# design.net
KiCad netlist of a schematic drawn in Altium Designer
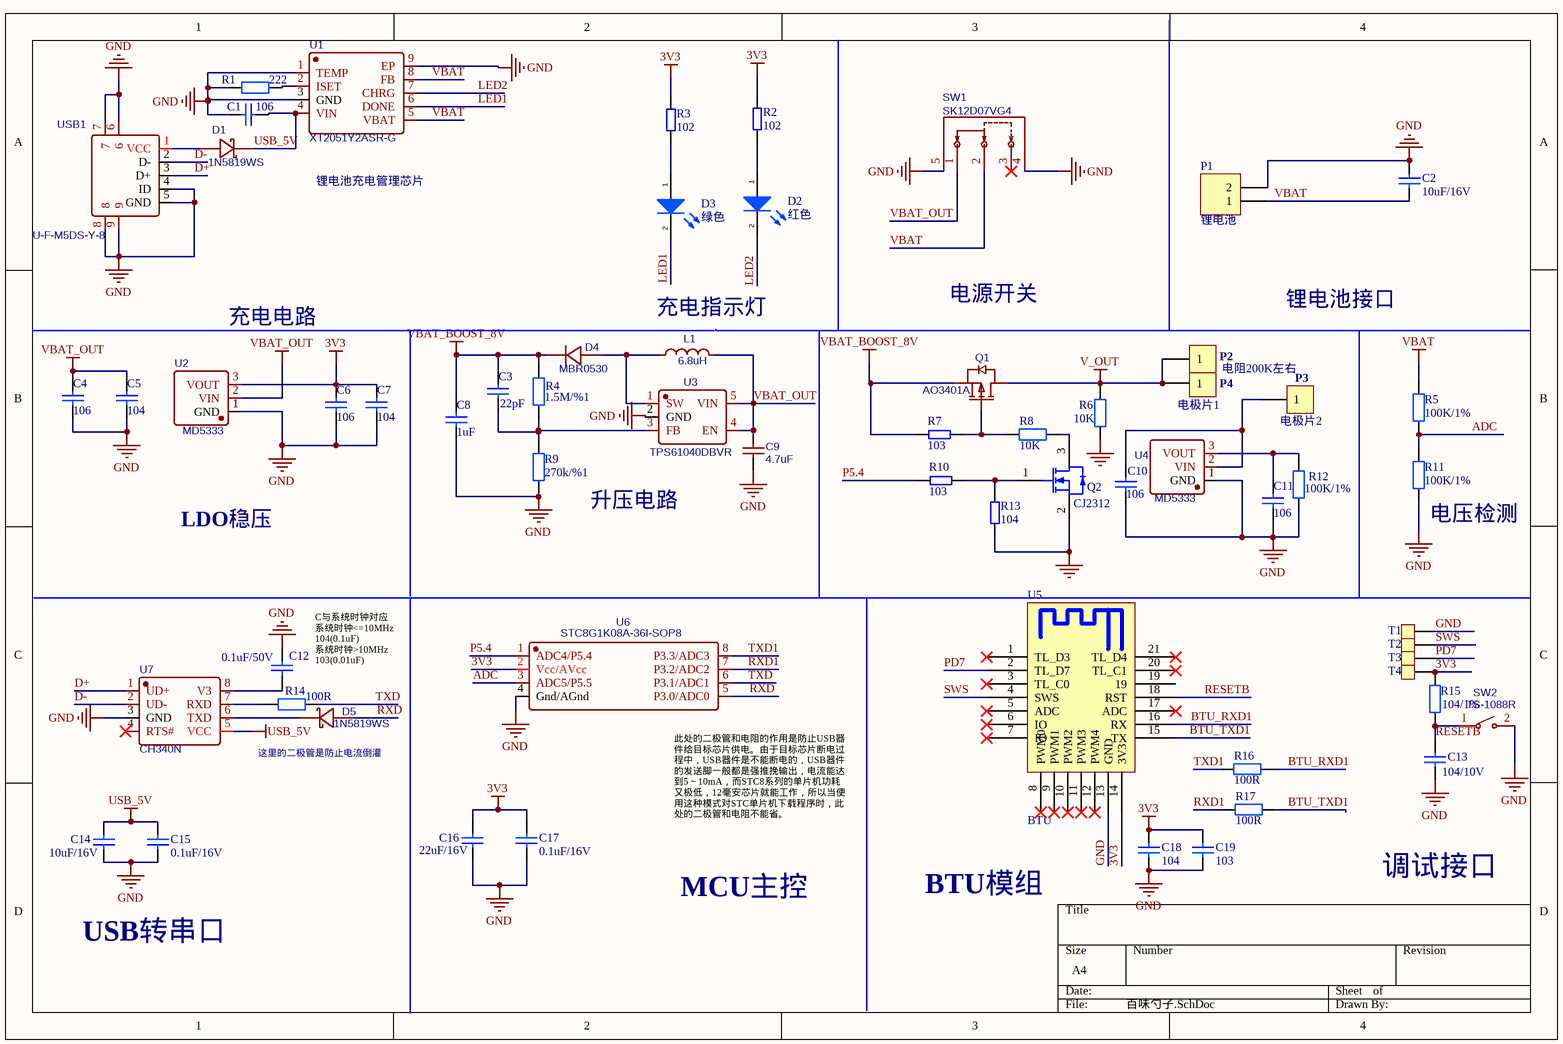
[diagram p0: 百味勺子.SchDoc]

(export (version "E")
  (design (tool "Eeschema 10.0.6"))
  (components
    (comp (ref "C1")
      (value "106")
      (footprint "C0603")
      (description "无极性电容")
      (fields (field (name "PART NUMBER") "1.02.03.00181") (field (name "修改人") "system"))
      (libsource (lib "Database_Libs") (part "Capacitor - non polarized"))
    )
    (comp (ref "C2")
      (value "10uF/16V")
      (footprint "C0603")
      (description "无极性电容")
      (fields (field (name "PART NUMBER") "1.02.05.00869"))
      (libsource (lib "咸味勺子-20210715") (part "Capacitor - non polarized"))
    )
    (comp (ref "C3")
      (value "22pF")
      (footprint "C0402")
      (description "无极性电容")
      (fields (field (name "PART NUMBER") "1.02.05.00869"))
      (libsource (lib "Database_Libs4") (part "Capacitor - non polarized"))
    )
    (comp (ref "C4")
      (value "106")
      (footprint "C0603")
      (description "无极性电容")
      (fields (field (name "PART NUMBER") "1.02.05.00869"))
      (libsource (lib "Database_Libs4") (part "Capacitor - non polarized"))
    )
    (comp (ref "C5")
      (value "104")
      (footprint "C0402")
      (description "无极性电容")
      (fields (field (name "PART NUMBER") "1.02.05.00869"))
      (libsource (lib "Database_Libs4") (part "Capacitor - non polarized"))
    )
    (comp (ref "C6")
      (value "106")
      (footprint "C0603")
      (description "无极性电容")
      (fields (field (name "PART NUMBER") "1.02.05.00869"))
      (libsource (lib "Database_Libs4") (part "Capacitor - non polarized"))
    )
    (comp (ref "C7")
      (value "104")
      (footprint "C0402")
      (description "无极性电容")
      (fields (field (name "PART NUMBER") "1.02.05.00869"))
      (libsource (lib "Database_Libs4") (part "Capacitor - non polarized"))
    )
    (comp (ref "C8")
      (value "1uF")
      (footprint "C0603")
      (description "无极性电容")
      (fields (field (name "PART NUMBER") "1.02.05.00869"))
      (libsource (lib "Database_Libs4") (part "Capacitor - non polarized"))
    )
    (comp (ref "C9")
      (value "4.7uF")
      (footprint "JMK212BJ475KG-T")
      (fields
        (field (name "BOM_MANUFACTURER PART") "JMK212BJ475KG-T")
        (field (name "BOM_SUPPLIER PART") "C92788")
      )
      (libsource (lib "altium-import") (part "root_1_4.7uF_"))
    )
    (comp (ref "C10")
      (value "106")
      (footprint "C0603")
      (description "无极性电容")
      (fields (field (name "PART NUMBER") "1.02.05.00869"))
      (libsource (lib "Database_Libs4") (part "Capacitor - non polarized"))
    )
    (comp (ref "C11")
      (value "106")
      (footprint "C0603")
      (description "无极性电容")
      (fields (field (name "PART NUMBER") "1.02.05.00869"))
      (libsource (lib "Database_Libs4") (part "Capacitor - non polarized"))
    )
    (comp (ref "C12")
      (value "0.1uF/50V")
      (footprint "C0402")
      (description "无极性电容")
      (fields (field (name "PART NUMBER") "1.02.05.00834") (field (name "修改人") "system"))
      (libsource (lib "Database_Libs") (part "Capacitor - non polarized"))
    )
    (comp (ref "C13")
      (value "104/10V")
      (footprint "C0402")
      (description "无极性电容")
      (fields (field (name "PART NUMBER") "1.02.05.00869"))
      (libsource (lib "Database_Libs4") (part "Capacitor - non polarized"))
    )
    (comp (ref "C14")
      (value "10uF/16V")
      (footprint "C0603")
      (description "无极性电容")
      (fields (field (name "PART NUMBER") "1.02.03.00181") (field (name "修改人") "system"))
      (libsource (lib "Database_Libs") (part "Capacitor - non polarized"))
    )
    (comp (ref "C15")
      (value "0.1uF/16V")
      (footprint "C0402")
      (description "无极性电容")
      (fields (field (name "PART NUMBER") "1.02.05.00834") (field (name "修改人") "system"))
      (libsource (lib "Database_Libs") (part "Capacitor - non polarized"))
    )
    (comp (ref "C16")
      (value "22uF/16V")
      (footprint "C0603")
      (description "无极性电容")
      (fields (field (name "PART NUMBER") "1.02.03.00181") (field (name "修改人") "system"))
      (libsource (lib "Database_Libs") (part "Capacitor - non polarized"))
    )
    (comp (ref "C17")
      (value "0.1uF/16V")
      (footprint "C0402")
      (description "无极性电容")
      (fields (field (name "PART NUMBER") "1.02.05.00834") (field (name "修改人") "system"))
      (libsource (lib "Database_Libs") (part "Capacitor - non polarized"))
    )
    (comp (ref "C18")
      (value "104")
      (footprint "C0402")
      (description "无极性电容")
      (fields (field (name "PART NUMBER") "1.02.05.00869"))
      (libsource (lib "Database_Libs4") (part "Capacitor - non polarized"))
    )
    (comp (ref "C19")
      (value "103")
      (footprint "C0402")
      (description "无极性电容")
      (fields (field (name "PART NUMBER") "1.02.05.00869"))
      (libsource (lib "Database_Libs4") (part "Capacitor - non polarized"))
    )
    (comp (ref "D1")
      (value "1N5819WS")
      (footprint "1N5819WS")
      (fields (field (name "BOM_SUPPLIER PART") "C1884554") (field (name "CONTRIBUTOR") "LCSC"))
      (libsource (lib "altium-import") (part "root_2_1N5819WS_C1884554_"))
    )
    (comp (ref "D2")
      (value "红色")
      (footprint "OSR50603C1E")
      (description "LED")
      (fields (field (name "PART NUMBER") "1.06.02.00452"))
      (libsource (lib "咸味勺子-20210715") (part "LED"))
    )
    (comp (ref "D3")
      (value "绿色")
      (footprint "OSR50603C1E")
      (description "LED")
      (fields (field (name "PART NUMBER") "1.06.02.00452"))
      (libsource (lib "咸味勺子-20210715") (part "LED"))
    )
    (comp (ref "D4")
      (value "MBR0530")
      (footprint "MBR0530")
      (fields (field (name "BOM_SUPPLIER PART") "C475718") (field (name "CONTRIBUTOR") "LCSC"))
      (libsource (lib "altium-import") (part "root_0_MBR0530_C475718_"))
    )
    (comp (ref "D5")
      (value "1N5819WS")
      (footprint "1N5819WS")
      (fields (field (name "BOM_SUPPLIER PART") "C1884554") (field (name "CONTRIBUTOR") "LCSC"))
      (libsource (lib "altium-import") (part "root_0_1N5819WS_C1884554_"))
    )
    (comp (ref "L1")
      (value "6.8uH")
      (footprint "CDRH3D23NP-6R8PC")
      (fields
        (field (name "BOM_SUPPLIER PART") "C323532")
        (field (name "BOM_MANUFACTURER PART") "CDRH3D23NP-6R8PC")
        (field (name "CONTRIBUTOR") "LCSC")
      )
      (libsource (lib "altium-import") (part "root_0_6.8uH_"))
    )
    (comp (ref "P1")
      (value "锂电池")
      (footprint "HDR1X2")
      (description "Header, 2-Pin")
      (fields (field (name "PUBLISHER") "Altium Limited"))
      (libsource (lib "Miscellaneous Connectors") (part "Header 2"))
    )
    (comp (ref "P2") (value "CON1") (footprint "焊点1") (libsource (lib "智能烧水壶 -电源板") (part "CON1")))
    (comp (ref "P3") (value "CON1") (footprint "焊点1") (libsource (lib "智能烧水壶 -电源板") (part "CON1")))
    (comp (ref "P4") (value "CON1") (footprint "焊点1") (libsource (lib "智能烧水壶 -电源板") (part "CON1")))
    (comp (ref "Q1")
      (value "AO3401A")
      (footprint "AO3401A")
      (fields (field (name "BOM_SUPPLIER PART") "C700954") (field (name "CONTRIBUTOR") "LCSC"))
      (libsource (lib "altium-import") (part "root_1_mirrored_AO3401A_C700954_"))
    )
    (comp (ref "Q2")
      (value "CJ2312")
      (footprint "CJ2312")
      (description "N-Channel MOSFET")
      (fields
        (field (name "PART NUMBER") "1.06.11.00008")
        (field (name "ORCAD LIBRARY PATH") "‪Z:\\tuya_lib\\sch-lib\\DISCRETE.OLB")
        (field (name "修改人") "system")
      )
      (libsource (lib "Database_Libs") (part "MOSFET-N"))
    )
    (comp (ref "R1")
      (value "222")
      (footprint "R0402")
      (description "电阻")
      (fields (field (name "PART NUMBER") "1.01.01.00808"))
      (libsource (lib "Database_Libs4") (part "Resistor"))
    )
    (comp (ref "R2")
      (value "102")
      (footprint "R0402")
      (description "RES")
      (libsource (lib "咸味勺子-20210715") (part "RES-1"))
    )
    (comp (ref "R3")
      (value "102")
      (footprint "R0402")
      (description "RES")
      (libsource (lib "咸味勺子-20210715") (part "RES-1"))
    )
    (comp (ref "R4")
      (value "1.5M/%1")
      (footprint "R0402")
      (description "电阻")
      (libsource (lib "Database_Libs") (part "Resistor"))
    )
    (comp (ref "R5")
      (value "100K/1%")
      (footprint "R0402")
      (description "电阻")
      (libsource (lib "Database_Libs") (part "Resistor"))
    )
    (comp (ref "R6")
      (value "10K")
      (footprint "R0402")
      (description "电阻")
      (libsource (lib "") (part "Resistor_2"))
    )
    (comp (ref "R7")
      (value "103")
      (footprint "R0402")
      (description "RES")
      (libsource (lib "先锋器件封装库") (part "RES-1"))
    )
    (comp (ref "R8")
      (value "10K")
      (footprint "R0402")
      (description "电阻")
      (libsource (lib "") (part "Resistor_1"))
    )
    (comp (ref "R9")
      (value "270k/%1")
      (footprint "R0402")
      (description "电阻")
      (libsource (lib "Database_Libs") (part "Resistor"))
    )
    (comp (ref "R10")
      (value "103")
      (footprint "R0402")
      (description "RES")
      (libsource (lib "先锋器件封装库") (part "RES-1"))
    )
    (comp (ref "R11")
      (value "100K/1%")
      (footprint "R0402")
      (description "电阻")
      (libsource (lib "Database_Libs") (part "Resistor"))
    )
    (comp (ref "R12")
      (value "100K/1%")
      (footprint "R0402")
      (description "电阻")
      (libsource (lib "Database_Libs") (part "Resistor"))
    )
    (comp (ref "R13")
      (value "104")
      (footprint "R0402")
      (description "RES")
      (libsource (lib "先锋器件封装库") (part "RES-1"))
    )
    (comp (ref "R14")
      (value "100R")
      (footprint "R0402")
      (description "电阻")
      (fields (field (name "PART NUMBER") "1.01.01.00808") (field (name "修改人") "system"))
      (libsource (lib "") (part "Resistor_1"))
    )
    (comp (ref "R15")
      (value "104/1%")
      (footprint "R0402")
      (description "电阻")
      (fields (field (name "PART NUMBER") "1.01.01.00808"))
      (libsource (lib "") (part "Resistor_1"))
    )
    (comp (ref "R16")
      (value "100R")
      (footprint "R0402")
      (description "电阻")
      (fields (field (name "PART NUMBER") "1.01.01.00808"))
      (libsource (lib "Database_Libs4") (part "Resistor"))
    )
    (comp (ref "R17")
      (value "100R")
      (footprint "R0402")
      (description "电阻")
      (fields (field (name "PART NUMBER") "1.01.01.00808"))
      (libsource (lib "Database_Libs4") (part "Resistor"))
    )
    (comp (ref "SW1")
      (value "SK12D07VG4")
      (footprint "SK12D07VG4")
      (fields (field (name "BOM_SUPPLIER PART") "C393937") (field (name "CONTRIBUTOR") "LCSC"))
      (libsource (lib "咸味勺子-20210715") (part "SK12D07VG4"))
    )
    (comp (ref "SW2")
      (value "TS-1088R")
      (footprint "TS-1088R-02026")
      (fields
        (field (name "BOM_SUPPLIER PART") "C455280")
        (field (name "BOM_MANUFACTURER PART") "TS-1088R-02026")
        (field (name "CONTRIBUTOR") "LCSC")
      )
      (libsource (lib "altium-import") (part "root_0_TS-1088R-02026_"))
    )
    (comp (ref "T1") (value "TP") (footprint "TP1") (libsource (lib "MIAXIS-SCH") (part "TP")))
    (comp (ref "T2") (value "TP") (footprint "TP1") (libsource (lib "MIAXIS-SCH") (part "TP")))
    (comp (ref "T3") (value "TP") (footprint "TP1") (libsource (lib "MIAXIS-SCH") (part "TP")))
    (comp (ref "T4") (value "TP") (footprint "TP1") (libsource (lib "MIAXIS-SCH") (part "TP")))
    (comp (ref "U1")
      (value "XT2051Y2ASR-G")
      (footprint "XT2051Y2ASR-G")
      (fields (field (name "BOM_SUPPLIER PART") "C236398") (field (name "CONTRIBUTOR") "LCSC"))
      (libsource (lib "altium-import") (part "root_0_XT2051Y2ASR-G_"))
    )
    (comp (ref "U2")
      (value "MD5333")
      (footprint "MD5333")
      (fields (field (name "BOM_SUPPLIER PART") "C2827936") (field (name "CONTRIBUTOR") "LCSC"))
      (libsource (lib "altium-import") (part "root_2_MD5333_"))
    )
    (comp (ref "U3")
      (value "TPS61040DBVR")
      (footprint "TPS61040DBVR")
      (fields (field (name "BOM_SUPPLIER PART") "C7722"))
      (libsource (lib "altium-import") (part "root_0_TPS61040DBVR_"))
    )
    (comp (ref "U4")
      (value "MD5333")
      (footprint "MD5333")
      (fields (field (name "BOM_SUPPLIER PART") "C2827936") (field (name "CONTRIBUTOR") "LCSC"))
      (libsource (lib "altium-import") (part "root_2_MD5333_"))
    )
    (comp (ref "U5")
      (value "BTU")
      (footprint "CBU1")
      (fields (field (name "PART NUMBER") "0110"))
      (libsource (lib "BTU_V100") (part "CBU"))
    )
    (comp (ref "U6")
      (value "STC8G1K08A-36I-SOP8")
      (footprint "STC8G1K08A-36I-SOP8")
      (fields (field (name "BOM_SUPPLIER PART") "C915663") (field (name "CONTRIBUTOR") "LCSC"))
      (libsource (lib "altium-import") (part "root_0_STC8G1K08A-36I-SOP8_"))
    )
    (comp (ref "U7")
      (value "CH340N")
      (footprint "CH340N")
      (fields (field (name "BOM_SUPPLIER PART") "C506813") (field (name "CONTRIBUTOR") "LCSC"))
      (libsource (lib "TY") (part "CH340N"))
    )
    (comp (ref "USB1")
      (value "U-F-M5DS-Y-8")
      (footprint "U-F-M5DS-Y-8")
      (fields (field (name "BOM_SUPPLIER PART") "C961761") (field (name "CONTRIBUTOR") "LCSC"))
      (libsource (lib "altium-import") (part "root_0_U-F-M5DS-Y-8_"))
    )
  )
  (nets
    (net (code "1") (name "/ADC") (class "Default")
      (node (ref "R11") (pin "2") (pinfunction "2_2") (pintype "passive"))
      (node (ref "R5") (pin "1") (pinfunction "1_1") (pintype "passive"))
      (node (ref "U6") (pin "3") (pinfunction "ADC5/P5.5_3") (pintype "passive"))
    )
    (net (code "2") (name "/BTU_RXD1") (class "Default")
      (node (ref "R16") (pin "1") (pinfunction "1_1") (pintype "passive"))
      (node (ref "U5") (pin "16") (pinfunction "RX_16") (pintype "passive"))
    )
    (net (code "3") (name "/BTU_TXD1") (class "Default")
      (node (ref "R17") (pin "1") (pinfunction "1_1") (pintype "passive"))
      (node (ref "U5") (pin "15") (pinfunction "TX_15") (pintype "passive"))
    )
    (net (code "4") (name "/D+") (class "Default")
      (node (ref "U7") (pin "1") (pinfunction "UD+_1") (pintype "passive"))
      (node (ref "USB1") (pin "3") (pinfunction "D+_3") (pintype "passive"))
    )
    (net (code "5") (name "/D-") (class "Default")
      (node (ref "U7") (pin "2") (pinfunction "UD-_2") (pintype "passive"))
      (node (ref "USB1") (pin "2") (pinfunction "D-_2") (pintype "passive"))
    )
    (net (code "6") (name "/LED1") (class "Default")
      (node (ref "D3") (pin "2") (pinfunction "2_2") (pintype "passive"))
      (node (ref "U1") (pin "6") (pinfunction "DONE_6") (pintype "passive"))
    )
    (net (code "7") (name "/LED2") (class "Default")
      (node (ref "D2") (pin "2") (pinfunction "2_2") (pintype "passive"))
      (node (ref "U1") (pin "7") (pinfunction "CHRG_7") (pintype "passive"))
    )
    (net (code "8") (name "/P5.4") (class "Default")
      (node (ref "R10") (pin "1") (pintype "passive"))
      (node (ref "U6") (pin "1") (pinfunction "ADC4/P5.4_1") (pintype "passive"))
    )
    (net (code "9") (name "/PD7") (class "Default")
      (node (ref "T3") (pin "1") (pinfunction "1_1") (pintype "passive"))
      (node (ref "U5") (pin "2") (pinfunction "TL_D7_2") (pintype "passive"))
    )
    (net (code "10") (name "/RESETB") (class "Default")
      (node (ref "C13") (pin "1") (pinfunction "1_1") (pintype "passive"))
      (node (ref "R15") (pin "1") (pinfunction "1_1") (pintype "passive"))
      (node (ref "SW2") (pin "1") (pinfunction "1_1") (pintype "passive"))
      (node (ref "U5") (pin "18") (pinfunction "RST_18") (pintype "passive"))
    )
    (net (code "11") (name "/RXD") (class "Default")
      (node (ref "D5") (pin "2") (pinfunction "A_2") (pintype "passive"))
      (node (ref "U6") (pin "5") (pinfunction "P3.0/ADC0_5") (pintype "passive"))
    )
    (net (code "12") (name "/RXD1") (class "Default")
      (node (ref "R17") (pin "2") (pinfunction "2_2") (pintype "passive"))
      (node (ref "U6") (pin "7") (pinfunction "P3.2/ADC2_7") (pintype "passive"))
    )
    (net (code "13") (name "/SWS") (class "Default")
      (node (ref "T2") (pin "1") (pinfunction "1_1") (pintype "passive"))
      (node (ref "U5") (pin "4") (pinfunction "SWS_4") (pintype "passive"))
    )
    (net (code "14") (name "/TXD") (class "Default")
      (node (ref "R14") (pin "2") (pinfunction "2_2") (pintype "passive"))
      (node (ref "U6") (pin "6") (pinfunction "P3.1/ADC1_6") (pintype "passive"))
    )
    (net (code "15") (name "/TXD1") (class "Default")
      (node (ref "R16") (pin "2") (pinfunction "2_2") (pintype "passive"))
      (node (ref "U6") (pin "8") (pinfunction "P3.3/ADC3_8") (pintype "passive"))
    )
    (net (code "16") (name "3V3") (class "Default")
      (node (ref "C16") (pin "2") (pinfunction "2_2") (pintype "passive"))
      (node (ref "C17") (pin "2") (pinfunction "2_2") (pintype "passive"))
      (node (ref "C18") (pin "1") (pinfunction "1_1") (pintype "passive"))
      (node (ref "C19") (pin "1") (pinfunction "1_1") (pintype "passive"))
      (node (ref "C6") (pin "1") (pinfunction "1_1") (pintype "passive"))
      (node (ref "C7") (pin "1") (pinfunction "1_1") (pintype "passive"))
      (node (ref "R15") (pin "2") (pinfunction "2_2") (pintype "passive"))
      (node (ref "R2") (pin "2") (pintype "passive"))
      (node (ref "R3") (pin "2") (pintype "passive"))
      (node (ref "T4") (pin "1") (pinfunction "1_1") (pintype "passive"))
      (node (ref "U2") (pin "3") (pinfunction "VOUT_3") (pintype "passive"))
      (node (ref "U5") (pin "14") (pinfunction "3V3_14") (pintype "passive"))
      (node (ref "U6") (pin "2") (pinfunction "Vcc/AVcc_2") (pintype "passive"))
    )
    (net (code "17") (name "GND") (class "Default")
      (node (ref "C1") (pin "2") (pinfunction "2_2") (pintype "passive"))
      (node (ref "C10") (pin "2") (pinfunction "2_2") (pintype "passive"))
      (node (ref "C11") (pin "2") (pinfunction "2_2") (pintype "passive"))
      (node (ref "C12") (pin "2") (pinfunction "2_2") (pintype "passive"))
      (node (ref "C13") (pin "2") (pinfunction "2_2") (pintype "passive"))
      (node (ref "C14") (pin "1") (pinfunction "1_1") (pintype "passive"))
      (node (ref "C15") (pin "1") (pinfunction "1_1") (pintype "passive"))
      (node (ref "C16") (pin "1") (pinfunction "1_1") (pintype "passive"))
      (node (ref "C17") (pin "1") (pinfunction "1_1") (pintype "passive"))
      (node (ref "C18") (pin "2") (pinfunction "2_2") (pintype "passive"))
      (node (ref "C19") (pin "2") (pinfunction "2_2") (pintype "passive"))
      (node (ref "C2") (pin "1") (pinfunction "1_1") (pintype "passive"))
      (node (ref "C4") (pin "2") (pinfunction "2_2") (pintype "passive"))
      (node (ref "C5") (pin "2") (pinfunction "2_2") (pintype "passive"))
      (node (ref "C6") (pin "2") (pinfunction "2_2") (pintype "passive"))
      (node (ref "C7") (pin "2") (pinfunction "2_2") (pintype "passive"))
      (node (ref "C8") (pin "2") (pinfunction "2_2") (pintype "passive"))
      (node (ref "C9") (pin "1") (pinfunction "1_1") (pintype "passive"))
      (node (ref "P1") (pin "2") (pinfunction "2_2") (pintype "passive"))
      (node (ref "Q2") (pin "2") (pinfunction "S_2") (pintype "passive"))
      (node (ref "R1") (pin "2") (pinfunction "2_2") (pintype "passive"))
      (node (ref "R11") (pin "1") (pinfunction "1_1") (pintype "passive"))
      (node (ref "R12") (pin "1") (pinfunction "1_1") (pintype "passive"))
      (node (ref "R13") (pin "1") (pintype "passive"))
      (node (ref "R6") (pin "2") (pinfunction "2_2") (pintype "passive"))
      (node (ref "R9") (pin "1") (pinfunction "1_1") (pintype "passive"))
      (node (ref "SW1") (pin "4") (pinfunction "4_4") (pintype "passive"))
      (node (ref "SW1") (pin "5") (pinfunction "5_5") (pintype "passive"))
      (node (ref "SW2") (pin "2") (pinfunction "2_2") (pintype "passive"))
      (node (ref "T1") (pin "1") (pinfunction "1_1") (pintype "passive"))
      (node (ref "U1") (pin "1") (pinfunction "TEMP_1") (pintype "passive"))
      (node (ref "U1") (pin "3") (pinfunction "GND_3") (pintype "passive"))
      (node (ref "U1") (pin "9") (pinfunction "EP_9") (pintype "passive"))
      (node (ref "U2") (pin "1") (pinfunction "GND_1") (pintype "passive"))
      (node (ref "U3") (pin "2") (pinfunction "GND_2") (pintype "passive"))
      (node (ref "U4") (pin "1") (pinfunction "GND_1") (pintype "passive"))
      (node (ref "U5") (pin "13") (pinfunction "GND_13") (pintype "passive"))
      (node (ref "U6") (pin "4") (pinfunction "Gnd/AGnd_4") (pintype "passive"))
      (node (ref "U7") (pin "3") (pinfunction "GND_3") (pintype "passive"))
      (node (ref "USB1") (pin "4") (pinfunction "ID_4") (pintype "passive"))
      (node (ref "USB1") (pin "5") (pinfunction "GND_5") (pintype "passive"))
      (node (ref "USB1") (pin "6") (pinfunction "6_6") (pintype "passive"))
      (node (ref "USB1") (pin "7") (pinfunction "7_7") (pintype "passive"))
      (node (ref "USB1") (pin "8") (pinfunction "8_8") (pintype "passive"))
      (node (ref "USB1") (pin "9") (pinfunction "9_9") (pintype "passive"))
    )
    (net (code "18") (name "Net-(D1-A)") (class "Default")
      (node (ref "D1") (pin "2") (pinfunction "A_2") (pintype "passive"))
      (node (ref "USB1") (pin "1") (pinfunction "VCC_1") (pintype "passive"))
    )
    (net (code "19") (name "Net-(D2-Pad1)") (class "Default")
      (node (ref "D2") (pin "1") (pinfunction "1_1") (pintype "passive"))
      (node (ref "R2") (pin "1") (pintype "passive"))
    )
    (net (code "20") (name "Net-(D3-Pad1)") (class "Default")
      (node (ref "D3") (pin "1") (pinfunction "1_1") (pintype "passive"))
      (node (ref "R3") (pin "1") (pintype "passive"))
    )
    (net (code "21") (name "Net-(D4-A)") (class "Default")
      (node (ref "D4") (pin "2") (pinfunction "A_2") (pintype "passive"))
      (node (ref "L1") (pin "1") (pinfunction "1_1") (pintype "passive"))
      (node (ref "U3") (pin "1") (pinfunction "SW_1") (pintype "passive"))
    )
    (net (code "22") (name "Net-(D5-C)") (class "Default")
      (node (ref "D5") (pin "1") (pinfunction "C_1") (pintype "passive"))
      (node (ref "U7") (pin "6") (pinfunction "TXD_6") (pintype "passive"))
    )
    (net (code "23") (name "Net-(Q1-G)") (class "Default")
      (node (ref "Q1") (pin "1") (pinfunction "G_1") (pintype "passive"))
      (node (ref "R7") (pin "2") (pintype "passive"))
      (node (ref "R8") (pin "1") (pinfunction "1_1") (pintype "passive"))
    )
    (net (code "24") (name "Net-(Q2-D)") (class "Default")
      (node (ref "Q2") (pin "3") (pinfunction "D_3") (pintype "passive"))
      (node (ref "R8") (pin "2") (pinfunction "2_2") (pintype "passive"))
    )
    (net (code "25") (name "Net-(Q2-G)") (class "Default")
      (node (ref "Q2") (pin "1") (pinfunction "G_1") (pintype "passive"))
      (node (ref "R10") (pin "2") (pintype "passive"))
      (node (ref "R13") (pin "2") (pintype "passive"))
    )
    (net (code "26") (name "Net-(U1-ISET)") (class "Default")
      (node (ref "R1") (pin "1") (pinfunction "1_1") (pintype "passive"))
      (node (ref "U1") (pin "2") (pinfunction "ISET_2") (pintype "passive"))
    )
    (net (code "27") (name "Net-(U3-FB)") (class "Default")
      (node (ref "C3") (pin "2") (pinfunction "2_2") (pintype "passive"))
      (node (ref "R4") (pin "1") (pinfunction "1_1") (pintype "passive"))
      (node (ref "R9") (pin "2") (pinfunction "2_2") (pintype "passive"))
      (node (ref "U3") (pin "3") (pinfunction "FB_3") (pintype "passive"))
    )
    (net (code "28") (name "Net-(U4-VIN)") (class "Default")
      (node (ref "C10") (pin "1") (pinfunction "1_1") (pintype "passive"))
      (node (ref "P3") (pin "1") (pinfunction "1_1") (pintype "passive"))
      (node (ref "U4") (pin "2") (pinfunction "VIN_2") (pintype "passive"))
    )
    (net (code "29") (name "Net-(U4-VOUT)") (class "Default")
      (node (ref "C11") (pin "1") (pinfunction "1_1") (pintype "passive"))
      (node (ref "R12") (pin "2") (pinfunction "2_2") (pintype "passive"))
      (node (ref "U4") (pin "3") (pinfunction "VOUT_3") (pintype "passive"))
    )
    (net (code "30") (name "Net-(U7-RXD)") (class "Default")
      (node (ref "R14") (pin "1") (pinfunction "1_1") (pintype "passive"))
      (node (ref "U7") (pin "7") (pinfunction "RXD_7") (pintype "passive"))
    )
    (net (code "31") (name "Net-(U7-V3)") (class "Default")
      (node (ref "C12") (pin "1") (pinfunction "1_1") (pintype "passive"))
      (node (ref "U7") (pin "8") (pinfunction "V3_8") (pintype "passive"))
    )
    (net (code "32") (name "USB_5V") (class "Default")
      (node (ref "C1") (pin "1") (pinfunction "1_1") (pintype "passive"))
      (node (ref "C14") (pin "2") (pinfunction "2_2") (pintype "passive"))
      (node (ref "C15") (pin "2") (pinfunction "2_2") (pintype "passive"))
      (node (ref "D1") (pin "1") (pinfunction "C_1") (pintype "passive"))
      (node (ref "U1") (pin "4") (pinfunction "VIN_4") (pintype "passive"))
      (node (ref "U7") (pin "5") (pinfunction "VCC_5") (pintype "passive"))
    )
    (net (code "33") (name "VBAT") (class "Default")
      (node (ref "C2") (pin "2") (pinfunction "2_2") (pintype "passive"))
      (node (ref "P1") (pin "1") (pinfunction "1_1") (pintype "passive"))
      (node (ref "R5") (pin "2") (pinfunction "2_2") (pintype "passive"))
      (node (ref "SW1") (pin "2") (pinfunction "2_2") (pintype "passive"))
      (node (ref "U1") (pin "5") (pinfunction "VBAT_5") (pintype "passive"))
      (node (ref "U1") (pin "8") (pinfunction "FB_8") (pintype "passive"))
    )
    (net (code "34") (name "VBAT_BOOST_8V") (class "Default")
      (node (ref "C3") (pin "1") (pinfunction "1_1") (pintype "passive"))
      (node (ref "C8") (pin "1") (pinfunction "1_1") (pintype "passive"))
      (node (ref "D4") (pin "1") (pinfunction "K_1") (pintype "passive"))
      (node (ref "Q1") (pin "2") (pinfunction "S_2") (pintype "passive"))
      (node (ref "R4") (pin "2") (pinfunction "2_2") (pintype "passive"))
      (node (ref "R7") (pin "1") (pintype "passive"))
    )
    (net (code "35") (name "VBAT_OUT") (class "Default")
      (node (ref "C4") (pin "1") (pinfunction "1_1") (pintype "passive"))
      (node (ref "C5") (pin "1") (pinfunction "1_1") (pintype "passive"))
      (node (ref "C9") (pin "2") (pinfunction "2_2") (pintype "passive"))
      (node (ref "L1") (pin "2") (pinfunction "2_2") (pintype "passive"))
      (node (ref "SW1") (pin "1") (pinfunction "1_1") (pintype "passive"))
      (node (ref "U2") (pin "2") (pinfunction "VIN_2") (pintype "passive"))
      (node (ref "U3") (pin "4") (pinfunction "EN_4") (pintype "passive"))
      (node (ref "U3") (pin "5") (pinfunction "VIN_5") (pintype "passive"))
    )
    (net (code "36") (name "V_OUT") (class "Default")
      (node (ref "P2") (pin "1") (pinfunction "1_1") (pintype "passive"))
      (node (ref "P4") (pin "1") (pinfunction "1_1") (pintype "passive"))
      (node (ref "Q1") (pin "3") (pinfunction "D_3") (pintype "passive"))
      (node (ref "R6") (pin "1") (pinfunction "1_1") (pintype "passive"))
    )
    (net (code "37") (name "unconnected-(SW1-Pad3)") (class "Default")
      (node (ref "SW1") (pin "3") (pinfunction "3_3") (pintype "passive+no_connect"))
    )
    (net (code "38") (name "unconnected-(U5-ADC-Pad5)") (class "Default")
      (node (ref "U5") (pin "5") (pinfunction "ADC_5") (pintype "passive+no_connect"))
    )
    (net (code "39") (name "unconnected-(U5-ADC-Pad17)") (class "Default")
      (node (ref "U5") (pin "17") (pinfunction "ADC_17") (pintype "passive+no_connect"))
    )
    (net (code "40") (name "unconnected-(U5-IO-Pad6)") (class "Default")
      (node (ref "U5") (pin "6") (pinfunction "IO_6") (pintype "passive+no_connect"))
    )
    (net (code "41") (name "unconnected-(U5-IO-Pad7)") (class "Default")
      (node (ref "U5") (pin "7") (pinfunction "IO_7") (pintype "passive+no_connect"))
    )
    (net (code "42") (name "unconnected-(U5-PWM0-Pad8)") (class "Default")
      (node (ref "U5") (pin "8") (pinfunction "PWM0_8") (pintype "passive+no_connect"))
    )
    (net (code "43") (name "unconnected-(U5-PWM1-Pad9)") (class "Default")
      (node (ref "U5") (pin "9") (pinfunction "PWM1_9") (pintype "passive+no_connect"))
    )
    (net (code "44") (name "unconnected-(U5-PWM2-Pad10)") (class "Default")
      (node (ref "U5") (pin "10") (pinfunction "PWM2_10") (pintype "passive+no_connect"))
    )
    (net (code "45") (name "unconnected-(U5-PWM3-Pad11)") (class "Default")
      (node (ref "U5") (pin "11") (pinfunction "PWM3_11") (pintype "passive+no_connect"))
    )
    (net (code "46") (name "unconnected-(U5-PWM4-Pad12)") (class "Default")
      (node (ref "U5") (pin "12") (pinfunction "PWM4_12") (pintype "passive+no_connect"))
    )
    (net (code "47") (name "unconnected-(U5-Pad19)") (class "Default")
      (node (ref "U5") (pin "19") (pinfunction "19_19") (pintype "passive"))
    )
    (net (code "48") (name "unconnected-(U5-TL_C0-Pad3)") (class "Default")
      (node (ref "U5") (pin "3") (pinfunction "TL_C0_3") (pintype "passive+no_connect"))
    )
    (net (code "49") (name "unconnected-(U5-TL_C1-Pad20)") (class "Default")
      (node (ref "U5") (pin "20") (pinfunction "TL_C1_20") (pintype "passive+no_connect"))
    )
    (net (code "50") (name "unconnected-(U5-TL_D3-Pad1)") (class "Default")
      (node (ref "U5") (pin "1") (pinfunction "TL_D3_1") (pintype "passive+no_connect"))
    )
    (net (code "51") (name "unconnected-(U5-TL_D4-Pad21)") (class "Default")
      (node (ref "U5") (pin "21") (pinfunction "TL_D4_21") (pintype "passive+no_connect"))
    )
    (net (code "52") (name "unconnected-(U7-RTS#-Pad4)") (class "Default")
      (node (ref "U7") (pin "4") (pinfunction "RTS#_4") (pintype "passive+no_connect"))
    )
  )
)
